# SCH_W-F-FC-H2XX.net
KiCad netlist of a schematic drawn in Altium Designer
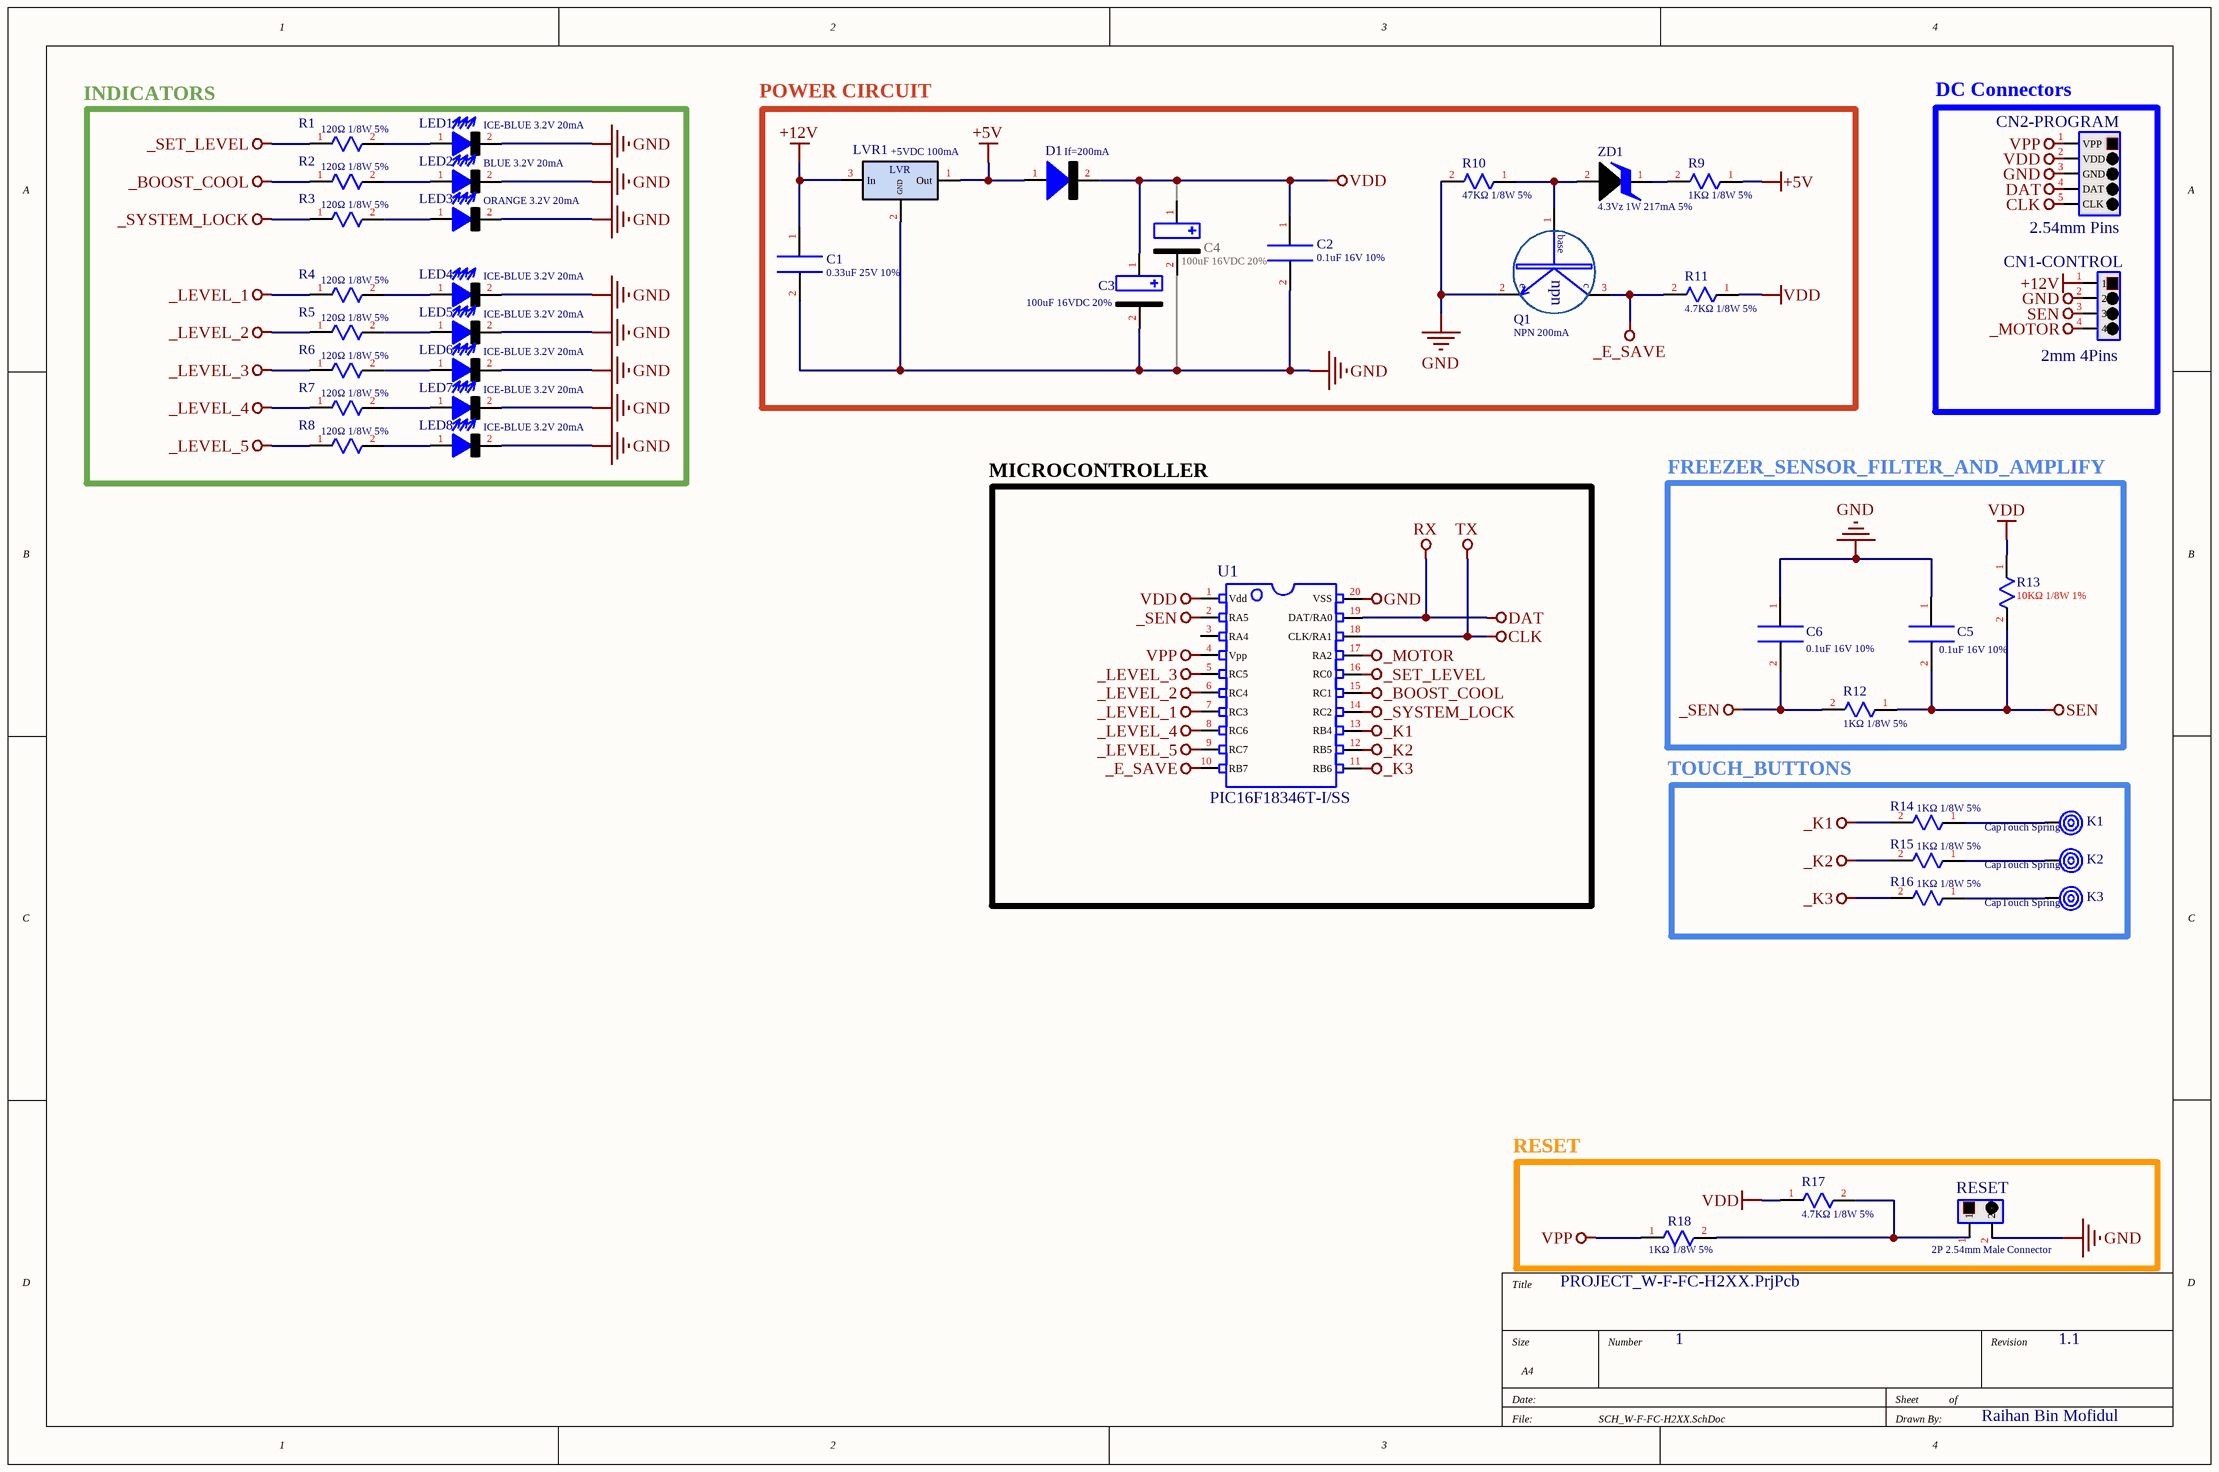
[diagram p0: SCH_W-F-FC-H2XX.SchDoc]

(export (version "E")
  (design (tool "Eeschema 10.0.6"))
  (components
    (comp (ref "C1")
      (value "0.33uF 25V 10%")
      (footprint "C_0805")
      (description "Multilayer Ceramic Capacitors, SMD 0805")
      (libsource (lib "RBM_SCH-Lib_16-Apr-19") (part "Capacitor Non-Polar"))
    )
    (comp (ref "C2")
      (value "0.1uF 16V 10%")
      (footprint "C_0805")
      (description "Multilayer Ceramic Capacitors, SMD 0805")
      (libsource (lib "RBM_SCH-Lib_16-Apr-19") (part "Capacitor Non-Polar"))
    )
    (comp (ref "C3")
      (value "100uF 16VDC 20%")
      (footprint "C_SMD_6.3X5.4_CK-100uF-16V")
      (description "Aluminum Electrolytic Capacitor, SMD ØDxL=6.3x5.4mm")
      (libsource (lib "RBM_SCH-LIB_02-SEP-19") (part "Capacitor Polar"))
    )
    (comp (ref "C4")
      (value "100uF 16VDC 20%")
      (footprint "C_Radial_P2_Right_Angle_without_3d")
      (description "Aluminum Electrolytic Capacitor, Through Hole, ØDxL=5*11mm Pitch=2mm")
      (libsource (lib "RBM_SCH-LIB_02-SEP-19") (part "Capacitor Polar"))
    )
    (comp (ref "C5")
      (value "0.1uF 16V 10%")
      (footprint "C_0805")
      (description "Multilayer Ceramic Capacitors, SMD 0805")
      (libsource (lib "RBM_SCH-Lib_16-Apr-19") (part "Capacitor Non-Polar"))
    )
    (comp (ref "C6")
      (value "0.1uF 16V 10%")
      (footprint "C_0805")
      (description "Multilayer Ceramic Capacitors, SMD 0805")
      (libsource (lib "RBM_SCH-Lib_16-Apr-19") (part "Capacitor Non-Polar"))
    )
    (comp (ref "CN1-CONTROL")
      (value "2mm 4Pins")
      (footprint "CN_4P_A2001WR-S-XP-LCP")
      (description "A2001WR-S-XP-LCP")
      (libsource (lib "RBM_SCH-LIB_02-SEP-19") (part "Connector_4PINs"))
    )
    (comp (ref "CN2-PROGRAM")
      (value "2.54mm Pins")
      (footprint "CN_PIC_MCU_Debugger_Straight")
      (libsource (lib "RBM_SCH-Lib_16-Apr-19") (part "Connector_PIC_Burn"))
    )
    (comp (ref "D1")
      (value "If=200mA")
      (footprint "D_SOT-23-3_200mA")
      (description "BAS19")
      (libsource (lib "RBM_SCH-LIB_02-SEP-19") (part "Diode"))
    )
    (comp (ref "K1")
      (value "CapTouch Spring")
      (footprint "K_TouchSpring-12H-9W-0.6&1.3D")
      (description "ØDxL=9x12mm LeadDia=0.6mm")
      (libsource (lib "RBM_SCH-LIB_02-SEP-19") (part "Touch_Spring"))
    )
    (comp (ref "K2")
      (value "CapTouch Spring")
      (footprint "K_TouchSpring-12H-9W-0.6&1.3D")
      (description "ØDxL=9x12mm LeadDia=0.6mm")
      (libsource (lib "RBM_SCH-LIB_02-SEP-19") (part "Touch_Spring"))
    )
    (comp (ref "K3")
      (value "CapTouch Spring")
      (footprint "K_TouchSpring-12H-9W-0.6&1.3D")
      (description "ØDxL=9x12mm LeadDia=0.6mm")
      (libsource (lib "RBM_SCH-LIB_02-SEP-19") (part "Touch_Spring"))
    )
    (comp (ref "LED1")
      (value "ICE-BLUE 3.2V 20mA")
      (footprint "LED_SMD3528")
      (description "WEJT28AC0-E74P01, SMD 3528")
      (libsource (lib "RBM_SCH-LIB_02-SEP-19") (part "LED"))
    )
    (comp (ref "LED2")
      (value "BLUE 3.2V 20mA")
      (footprint "LED_SMD3528")
      (description "WEJT28ABV-BCDP01, SMD 3528")
      (libsource (lib "RBM_SCH-LIB_02-SEP-19") (part "LED"))
    )
    (comp (ref "LED3")
      (value "ORANGE 3.2V 20mA")
      (footprint "LED_SMD3528")
      (description "WEJT28AAV-6ACP01, SMD 3528")
      (libsource (lib "RBM_SCH-LIB_02-SEP-19") (part "LED"))
    )
    (comp (ref "LED4")
      (value "ICE-BLUE 3.2V 20mA")
      (footprint "LED_SMD3528")
      (description "WEJT28AC0-E74P01, SMD 3528")
      (libsource (lib "RBM_SCH-LIB_02-SEP-19") (part "LED"))
    )
    (comp (ref "LED5")
      (value "ICE-BLUE 3.2V 20mA")
      (footprint "LED_SMD3528")
      (description "WEJT28AC0-E74P01, SMD 3528")
      (libsource (lib "RBM_SCH-LIB_02-SEP-19") (part "LED"))
    )
    (comp (ref "LED6")
      (value "ICE-BLUE 3.2V 20mA")
      (footprint "LED_SMD3528")
      (description "WEJT28AC0-E74P01, SMD 3528")
      (libsource (lib "RBM_SCH-LIB_02-SEP-19") (part "LED"))
    )
    (comp (ref "LED7")
      (value "ICE-BLUE 3.2V 20mA")
      (footprint "LED_SMD3528")
      (description "WEJT28AC0-E74P01, SMD 3528")
      (libsource (lib "RBM_SCH-LIB_02-SEP-19") (part "LED"))
    )
    (comp (ref "LED8")
      (value "ICE-BLUE 3.2V 20mA")
      (footprint "LED_SMD3528")
      (description "WEJT28AC0-E74P01, SMD 3528")
      (libsource (lib "RBM_SCH-LIB_02-SEP-19") (part "LED"))
    )
    (comp (ref "LVR1")
      (value "+5VDC 100mA")
      (footprint "U_CJ78L05_SOT89")
      (description "SOT-89-3L Plastic-Encapsulate Voltage Regulator")
      (libsource (lib "RBM_SCH-Lib_16-Apr-19") (part "Voltage Regulator"))
    )
    (comp (ref "Q1")
      (value "NPN 200mA")
      (footprint "Q_SOT-23-3_NPN_BC847")
      (description "BC847, SOT-23-3")
      (libsource (lib "RBM_SCH-Lib_16-Apr-19") (part "BJT_npn"))
    )
    (comp (ref "R1")
      (value "120Ω 1/8W 5%")
      (footprint "R_0805")
      (description "Chip-Resistor, SMD 0805, , RoHS")
      (libsource (lib "RBM_SCH-Lib_16-Apr-19") (part "Resistor"))
    )
    (comp (ref "R2")
      (value "120Ω 1/8W 5%")
      (footprint "R_0805")
      (description "Chip-Resistor, SMD 0805, , RoHS")
      (libsource (lib "RBM_SCH-Lib_16-Apr-19") (part "Resistor"))
    )
    (comp (ref "R3")
      (value "120Ω 1/8W 5%")
      (footprint "R_0805")
      (description "Chip-Resistor, SMD 0805, , RoHS")
      (libsource (lib "RBM_SCH-Lib_16-Apr-19") (part "Resistor"))
    )
    (comp (ref "R4")
      (value "120Ω 1/8W 5%")
      (footprint "R_0805")
      (description "Chip-Resistor, SMD 0805, , RoHS")
      (libsource (lib "RBM_SCH-Lib_16-Apr-19") (part "Resistor"))
    )
    (comp (ref "R5")
      (value "120Ω 1/8W 5%")
      (footprint "R_0805")
      (description "Chip-Resistor, SMD 0805, , RoHS")
      (libsource (lib "RBM_SCH-Lib_16-Apr-19") (part "Resistor"))
    )
    (comp (ref "R6")
      (value "120Ω 1/8W 5%")
      (footprint "R_0805")
      (description "Chip-Resistor, SMD 0805, , RoHS")
      (libsource (lib "RBM_SCH-Lib_16-Apr-19") (part "Resistor"))
    )
    (comp (ref "R7")
      (value "120Ω 1/8W 5%")
      (footprint "R_0805")
      (description "Chip-Resistor, SMD 0805, , RoHS")
      (libsource (lib "RBM_SCH-Lib_16-Apr-19") (part "Resistor"))
    )
    (comp (ref "R8")
      (value "120Ω 1/8W 5%")
      (footprint "R_0805")
      (description "Chip-Resistor, SMD 0805, , RoHS")
      (libsource (lib "RBM_SCH-Lib_16-Apr-19") (part "Resistor"))
    )
    (comp (ref "R9")
      (value "1KΩ 1/8W 5%")
      (footprint "R_0805")
      (description "Chip-Resistor, SMD 0805, , RoHS")
      (libsource (lib "RBM_SCH-Lib_16-Apr-19") (part "Resistor"))
    )
    (comp (ref "R10")
      (value "47KΩ 1/8W 5%")
      (footprint "R_0805")
      (description "Chip-Resistor, SMD 0805, , RoHS")
      (libsource (lib "RBM_SCH-Lib_16-Apr-19") (part "Resistor"))
    )
    (comp (ref "R11")
      (value "4.7KΩ 1/8W 5%")
      (footprint "R_0805")
      (description "Chip-Resistor, SMD 0805, , RoHS")
      (libsource (lib "RBM_SCH-Lib_16-Apr-19") (part "Resistor"))
    )
    (comp (ref "R12")
      (value "1KΩ 1/8W 5%")
      (footprint "R_0805")
      (description "Chip-Resistor, SMD 0805, , RoHS")
      (libsource (lib "") (part "Resistor_1"))
    )
    (comp (ref "R13")
      (value "10KΩ 1/8W 1%")
      (footprint "R_0805")
      (description "Chip-Resistor, SMD 0805, , RoHS")
      (libsource (lib "RBM_SCH-Lib_16-Apr-19") (part "Resistor"))
    )
    (comp (ref "R14")
      (value "1KΩ 1/8W 5%")
      (footprint "R_0805")
      (description "Chip-Resistor, SMD 0805, , RoHS")
      (libsource (lib "") (part "Resistor_2"))
    )
    (comp (ref "R15")
      (value "1KΩ 1/8W 5%")
      (footprint "R_0805")
      (description "Chip-Resistor, SMD 0805, , RoHS")
      (libsource (lib "") (part "Resistor_2"))
    )
    (comp (ref "R16")
      (value "1KΩ 1/8W 5%")
      (footprint "R_0805")
      (description "Chip-Resistor, SMD 0805, , RoHS")
      (libsource (lib "") (part "Resistor_2"))
    )
    (comp (ref "R17")
      (value "4.7KΩ 1/8W 5%")
      (footprint "R_0805")
      (description "Chip-Resistor, SMD 0805, , RoHS")
      (libsource (lib "RBM_SCH-Lib_16-Apr-19") (part "Resistor"))
    )
    (comp (ref "R18")
      (value "1KΩ 1/8W 5%")
      (footprint "R_0805")
      (description "Chip-Resistor, SMD 0805, , RoHS")
      (libsource (lib "RBM_SCH-Lib_16-Apr-19") (part "Resistor"))
    )
    (comp (ref "RESET")
      (value "2P 2.54mm Male Connector")
      (footprint "CN_PIC_MCU_Reseter_Straight")
      (libsource (lib "RBM_SCH-LIB_02-SEP-19") (part "Connector_2PINs"))
    )
    (comp (ref "U1")
      (value "PIC16F18346T-I/SS")
      (footprint "U_PIC_20pin_SSOP")
      (libsource (lib "RBM_SCH-LIB_02-SEP-19") (part "IC_PIC_20pins"))
    )
    (comp (ref "ZD1")
      (value "4.3Vz 1W 217mA 5%")
      (footprint "ZD_ZM4742A LL-41")
      (description "ZM4731, MELF SILICON PLANAR POWER ZENER DIODES, LL-41")
      (libsource (lib "RBM_SCH-Lib_28-Mar-19") (part "Zener Diode"))
    )
  )
  (nets
    (net (code "1") (name "+5V") (class "Default")
      (node (ref "D1") (pin "1") (pinfunction "vdd_1") (pintype "passive"))
      (node (ref "LVR1") (pin "1") (pinfunction "Out_1") (pintype "passive"))
      (node (ref "R9") (pin "1") (pinfunction "1_1") (pintype "passive"))
    )
    (net (code "2") (name "+12V") (class "Default")
      (node (ref "C1") (pin "1") (pinfunction "1_1") (pintype "passive"))
      (node (ref "CN1-CONTROL") (pin "1") (pinfunction "1_1") (pintype "passive"))
      (node (ref "LVR1") (pin "3") (pinfunction "In_3") (pintype "passive"))
    )
    (net (code "3") (name "CLK") (class "Default")
      (node (ref "CN2-PROGRAM") (pin "5") (pinfunction "CLK_5") (pintype "passive"))
      (node (ref "U1") (pin "18") (pinfunction "CLK/RA1_18") (pintype "passive"))
    )
    (net (code "4") (name "DAT") (class "Default")
      (node (ref "CN2-PROGRAM") (pin "4") (pinfunction "DAT_4") (pintype "passive"))
      (node (ref "U1") (pin "19") (pinfunction "DAT/RA0_19") (pintype "passive"))
    )
    (net (code "5") (name "GND") (class "Default")
      (node (ref "C1") (pin "2") (pinfunction "2_2") (pintype "passive"))
      (node (ref "C2") (pin "2") (pinfunction "2_2") (pintype "passive"))
      (node (ref "C3") (pin "2") (pinfunction "vss_2") (pintype "passive"))
      (node (ref "C4") (pin "2") (pinfunction "vss_2") (pintype "passive"))
      (node (ref "C5") (pin "1") (pinfunction "1_1") (pintype "passive"))
      (node (ref "C6") (pin "1") (pinfunction "1_1") (pintype "passive"))
      (node (ref "CN1-CONTROL") (pin "2") (pinfunction "2_2") (pintype "passive"))
      (node (ref "CN2-PROGRAM") (pin "3") (pinfunction "GND_3") (pintype "passive"))
      (node (ref "LED1") (pin "2") (pinfunction "vss_2") (pintype "passive"))
      (node (ref "LED2") (pin "2") (pinfunction "vss_2") (pintype "passive"))
      (node (ref "LED3") (pin "2") (pinfunction "vss_2") (pintype "passive"))
      (node (ref "LED4") (pin "2") (pinfunction "vss_2") (pintype "passive"))
      (node (ref "LED5") (pin "2") (pinfunction "vss_2") (pintype "passive"))
      (node (ref "LED6") (pin "2") (pinfunction "vss_2") (pintype "passive"))
      (node (ref "LED7") (pin "2") (pinfunction "vss_2") (pintype "passive"))
      (node (ref "LED8") (pin "2") (pinfunction "vss_2") (pintype "passive"))
      (node (ref "LVR1") (pin "2") (pinfunction "GND_2") (pintype "passive"))
      (node (ref "Q1") (pin "2") (pinfunction "Emitter_2") (pintype "passive"))
      (node (ref "R10") (pin "2") (pinfunction "2_2") (pintype "passive"))
      (node (ref "RESET") (pin "2") (pinfunction "2_2") (pintype "passive"))
      (node (ref "U1") (pin "20") (pinfunction "VSS_20") (pintype "passive"))
    )
    (net (code "6") (name "Net-(K1-Pad1)") (class "Default")
      (node (ref "K1") (pin "1") (pinfunction "1_1") (pintype "passive"))
      (node (ref "R14") (pin "1") (pinfunction "1_1") (pintype "passive"))
    )
    (net (code "7") (name "Net-(K2-Pad1)") (class "Default")
      (node (ref "K2") (pin "1") (pinfunction "1_1") (pintype "passive"))
      (node (ref "R15") (pin "1") (pinfunction "1_1") (pintype "passive"))
    )
    (net (code "8") (name "Net-(K3-Pad1)") (class "Default")
      (node (ref "K3") (pin "1") (pinfunction "1_1") (pintype "passive"))
      (node (ref "R16") (pin "1") (pinfunction "1_1") (pintype "passive"))
    )
    (net (code "9") (name "Net-(LED1-vdd)") (class "Default")
      (node (ref "LED1") (pin "1") (pinfunction "vdd_1") (pintype "passive"))
      (node (ref "R1") (pin "2") (pinfunction "2_2") (pintype "passive"))
    )
    (net (code "10") (name "Net-(LED2-vdd)") (class "Default")
      (node (ref "LED2") (pin "1") (pinfunction "vdd_1") (pintype "passive"))
      (node (ref "R2") (pin "2") (pinfunction "2_2") (pintype "passive"))
    )
    (net (code "11") (name "Net-(LED3-vdd)") (class "Default")
      (node (ref "LED3") (pin "1") (pinfunction "vdd_1") (pintype "passive"))
      (node (ref "R3") (pin "2") (pinfunction "2_2") (pintype "passive"))
    )
    (net (code "12") (name "Net-(LED4-vdd)") (class "Default")
      (node (ref "LED4") (pin "1") (pinfunction "vdd_1") (pintype "passive"))
      (node (ref "R4") (pin "2") (pinfunction "2_2") (pintype "passive"))
    )
    (net (code "13") (name "Net-(LED5-vdd)") (class "Default")
      (node (ref "LED5") (pin "1") (pinfunction "vdd_1") (pintype "passive"))
      (node (ref "R5") (pin "2") (pinfunction "2_2") (pintype "passive"))
    )
    (net (code "14") (name "Net-(LED6-vdd)") (class "Default")
      (node (ref "LED6") (pin "1") (pinfunction "vdd_1") (pintype "passive"))
      (node (ref "R6") (pin "2") (pinfunction "2_2") (pintype "passive"))
    )
    (net (code "15") (name "Net-(LED7-vdd)") (class "Default")
      (node (ref "LED7") (pin "1") (pinfunction "vdd_1") (pintype "passive"))
      (node (ref "R7") (pin "2") (pinfunction "2_2") (pintype "passive"))
    )
    (net (code "16") (name "Net-(LED8-vdd)") (class "Default")
      (node (ref "LED8") (pin "1") (pinfunction "vdd_1") (pintype "passive"))
      (node (ref "R8") (pin "2") (pinfunction "2_2") (pintype "passive"))
    )
    (net (code "17") (name "Net-(Q1-Base)") (class "Default")
      (node (ref "Q1") (pin "1") (pinfunction "Base_1") (pintype "passive"))
      (node (ref "R10") (pin "1") (pinfunction "1_1") (pintype "passive"))
      (node (ref "ZD1") (pin "2") (pinfunction "GND_2") (pintype "passive"))
    )
    (net (code "18") (name "Net-(R17-Pad2)") (class "Default")
      (node (ref "R17") (pin "2") (pinfunction "2_2") (pintype "passive"))
      (node (ref "R18") (pin "2") (pinfunction "2_2") (pintype "passive"))
      (node (ref "RESET") (pin "1") (pinfunction "1_1") (pintype "passive"))
    )
    (net (code "19") (name "Net-(ZD1-VCC)") (class "Default")
      (node (ref "R9") (pin "2") (pinfunction "2_2") (pintype "passive"))
      (node (ref "ZD1") (pin "1") (pinfunction "VCC_1") (pintype "passive"))
    )
    (net (code "20") (name "SEN") (class "Default")
      (node (ref "C5") (pin "2") (pinfunction "2_2") (pintype "passive"))
      (node (ref "CN1-CONTROL") (pin "3") (pinfunction "3_3") (pintype "passive"))
      (node (ref "R12") (pin "1") (pinfunction "1_1") (pintype "passive"))
      (node (ref "R13") (pin "2") (pinfunction "2_2") (pintype "passive"))
    )
    (net (code "21") (name "VDD") (class "Default")
      (node (ref "C2") (pin "1") (pinfunction "1_1") (pintype "passive"))
      (node (ref "C3") (pin "1") (pinfunction "vdd_1") (pintype "passive"))
      (node (ref "C4") (pin "1") (pinfunction "vdd_1") (pintype "passive"))
      (node (ref "CN2-PROGRAM") (pin "2") (pinfunction "VDD_2") (pintype "passive"))
      (node (ref "D1") (pin "2") (pinfunction "vss_2") (pintype "passive"))
      (node (ref "R11") (pin "1") (pinfunction "1_1") (pintype "passive"))
      (node (ref "R13") (pin "1") (pinfunction "1_1") (pintype "passive"))
      (node (ref "R17") (pin "1") (pinfunction "1_1") (pintype "passive"))
      (node (ref "U1") (pin "1") (pinfunction "Vdd_1") (pintype "passive"))
    )
    (net (code "22") (name "VPP") (class "Default")
      (node (ref "CN2-PROGRAM") (pin "1") (pinfunction "VPP_1") (pintype "passive"))
      (node (ref "R18") (pin "1") (pinfunction "1_1") (pintype "passive"))
      (node (ref "U1") (pin "4") (pinfunction "Vpp_4") (pintype "passive"))
    )
    (net (code "23") (name "_BOOST_COOL") (class "Default")
      (node (ref "R2") (pin "1") (pinfunction "1_1") (pintype "passive"))
      (node (ref "U1") (pin "15") (pinfunction "RC1_15") (pintype "passive"))
    )
    (net (code "24") (name "_E_SAVE") (class "Default")
      (node (ref "Q1") (pin "3") (pinfunction "Collector_3") (pintype "passive"))
      (node (ref "R11") (pin "2") (pinfunction "2_2") (pintype "passive"))
      (node (ref "U1") (pin "10") (pinfunction "RB7_10") (pintype "passive"))
    )
    (net (code "25") (name "_K1") (class "Default")
      (node (ref "R14") (pin "2") (pinfunction "2_2") (pintype "passive"))
      (node (ref "U1") (pin "13") (pinfunction "RB4_13") (pintype "passive"))
    )
    (net (code "26") (name "_K2") (class "Default")
      (node (ref "R15") (pin "2") (pinfunction "2_2") (pintype "passive"))
      (node (ref "U1") (pin "12") (pinfunction "RB5_12") (pintype "passive"))
    )
    (net (code "27") (name "_K3") (class "Default")
      (node (ref "R16") (pin "2") (pinfunction "2_2") (pintype "passive"))
      (node (ref "U1") (pin "11") (pinfunction "RB6_11") (pintype "passive"))
    )
    (net (code "28") (name "_LEVEL_1") (class "Default")
      (node (ref "R4") (pin "1") (pinfunction "1_1") (pintype "passive"))
      (node (ref "U1") (pin "7") (pinfunction "RC3_7") (pintype "passive"))
    )
    (net (code "29") (name "_LEVEL_2") (class "Default")
      (node (ref "R5") (pin "1") (pinfunction "1_1") (pintype "passive"))
      (node (ref "U1") (pin "6") (pinfunction "RC4_6") (pintype "passive"))
    )
    (net (code "30") (name "_LEVEL_3") (class "Default")
      (node (ref "R6") (pin "1") (pinfunction "1_1") (pintype "passive"))
      (node (ref "U1") (pin "5") (pinfunction "RC5_5") (pintype "passive"))
    )
    (net (code "31") (name "_LEVEL_4") (class "Default")
      (node (ref "R7") (pin "1") (pinfunction "1_1") (pintype "passive"))
      (node (ref "U1") (pin "8") (pinfunction "RC6_8") (pintype "passive"))
    )
    (net (code "32") (name "_LEVEL_5") (class "Default")
      (node (ref "R8") (pin "1") (pinfunction "1_1") (pintype "passive"))
      (node (ref "U1") (pin "9") (pinfunction "RC7_9") (pintype "passive"))
    )
    (net (code "33") (name "_MOTOR") (class "Default")
      (node (ref "CN1-CONTROL") (pin "4") (pinfunction "4_4") (pintype "passive"))
      (node (ref "U1") (pin "17") (pinfunction "RA2_17") (pintype "passive"))
    )
    (net (code "34") (name "_SEN") (class "Default")
      (node (ref "C6") (pin "2") (pinfunction "2_2") (pintype "passive"))
      (node (ref "R12") (pin "2") (pinfunction "2_2") (pintype "passive"))
      (node (ref "U1") (pin "2") (pinfunction "RA5_2") (pintype "passive"))
    )
    (net (code "35") (name "_SET_LEVEL") (class "Default")
      (node (ref "R1") (pin "1") (pinfunction "1_1") (pintype "passive"))
      (node (ref "U1") (pin "16") (pinfunction "RC0_16") (pintype "passive"))
    )
    (net (code "36") (name "_SYSTEM_LOCK") (class "Default")
      (node (ref "R3") (pin "1") (pinfunction "1_1") (pintype "passive"))
      (node (ref "U1") (pin "14") (pinfunction "RC2_14") (pintype "passive"))
    )
    (net (code "37") (name "unconnected-(U1-RA4-Pad3)") (class "Default")
      (node (ref "U1") (pin "3") (pinfunction "RA4_3") (pintype "passive"))
    )
  )
)
